# schematic.net
KiCad netlist of a schematic drawn in EasyEDA
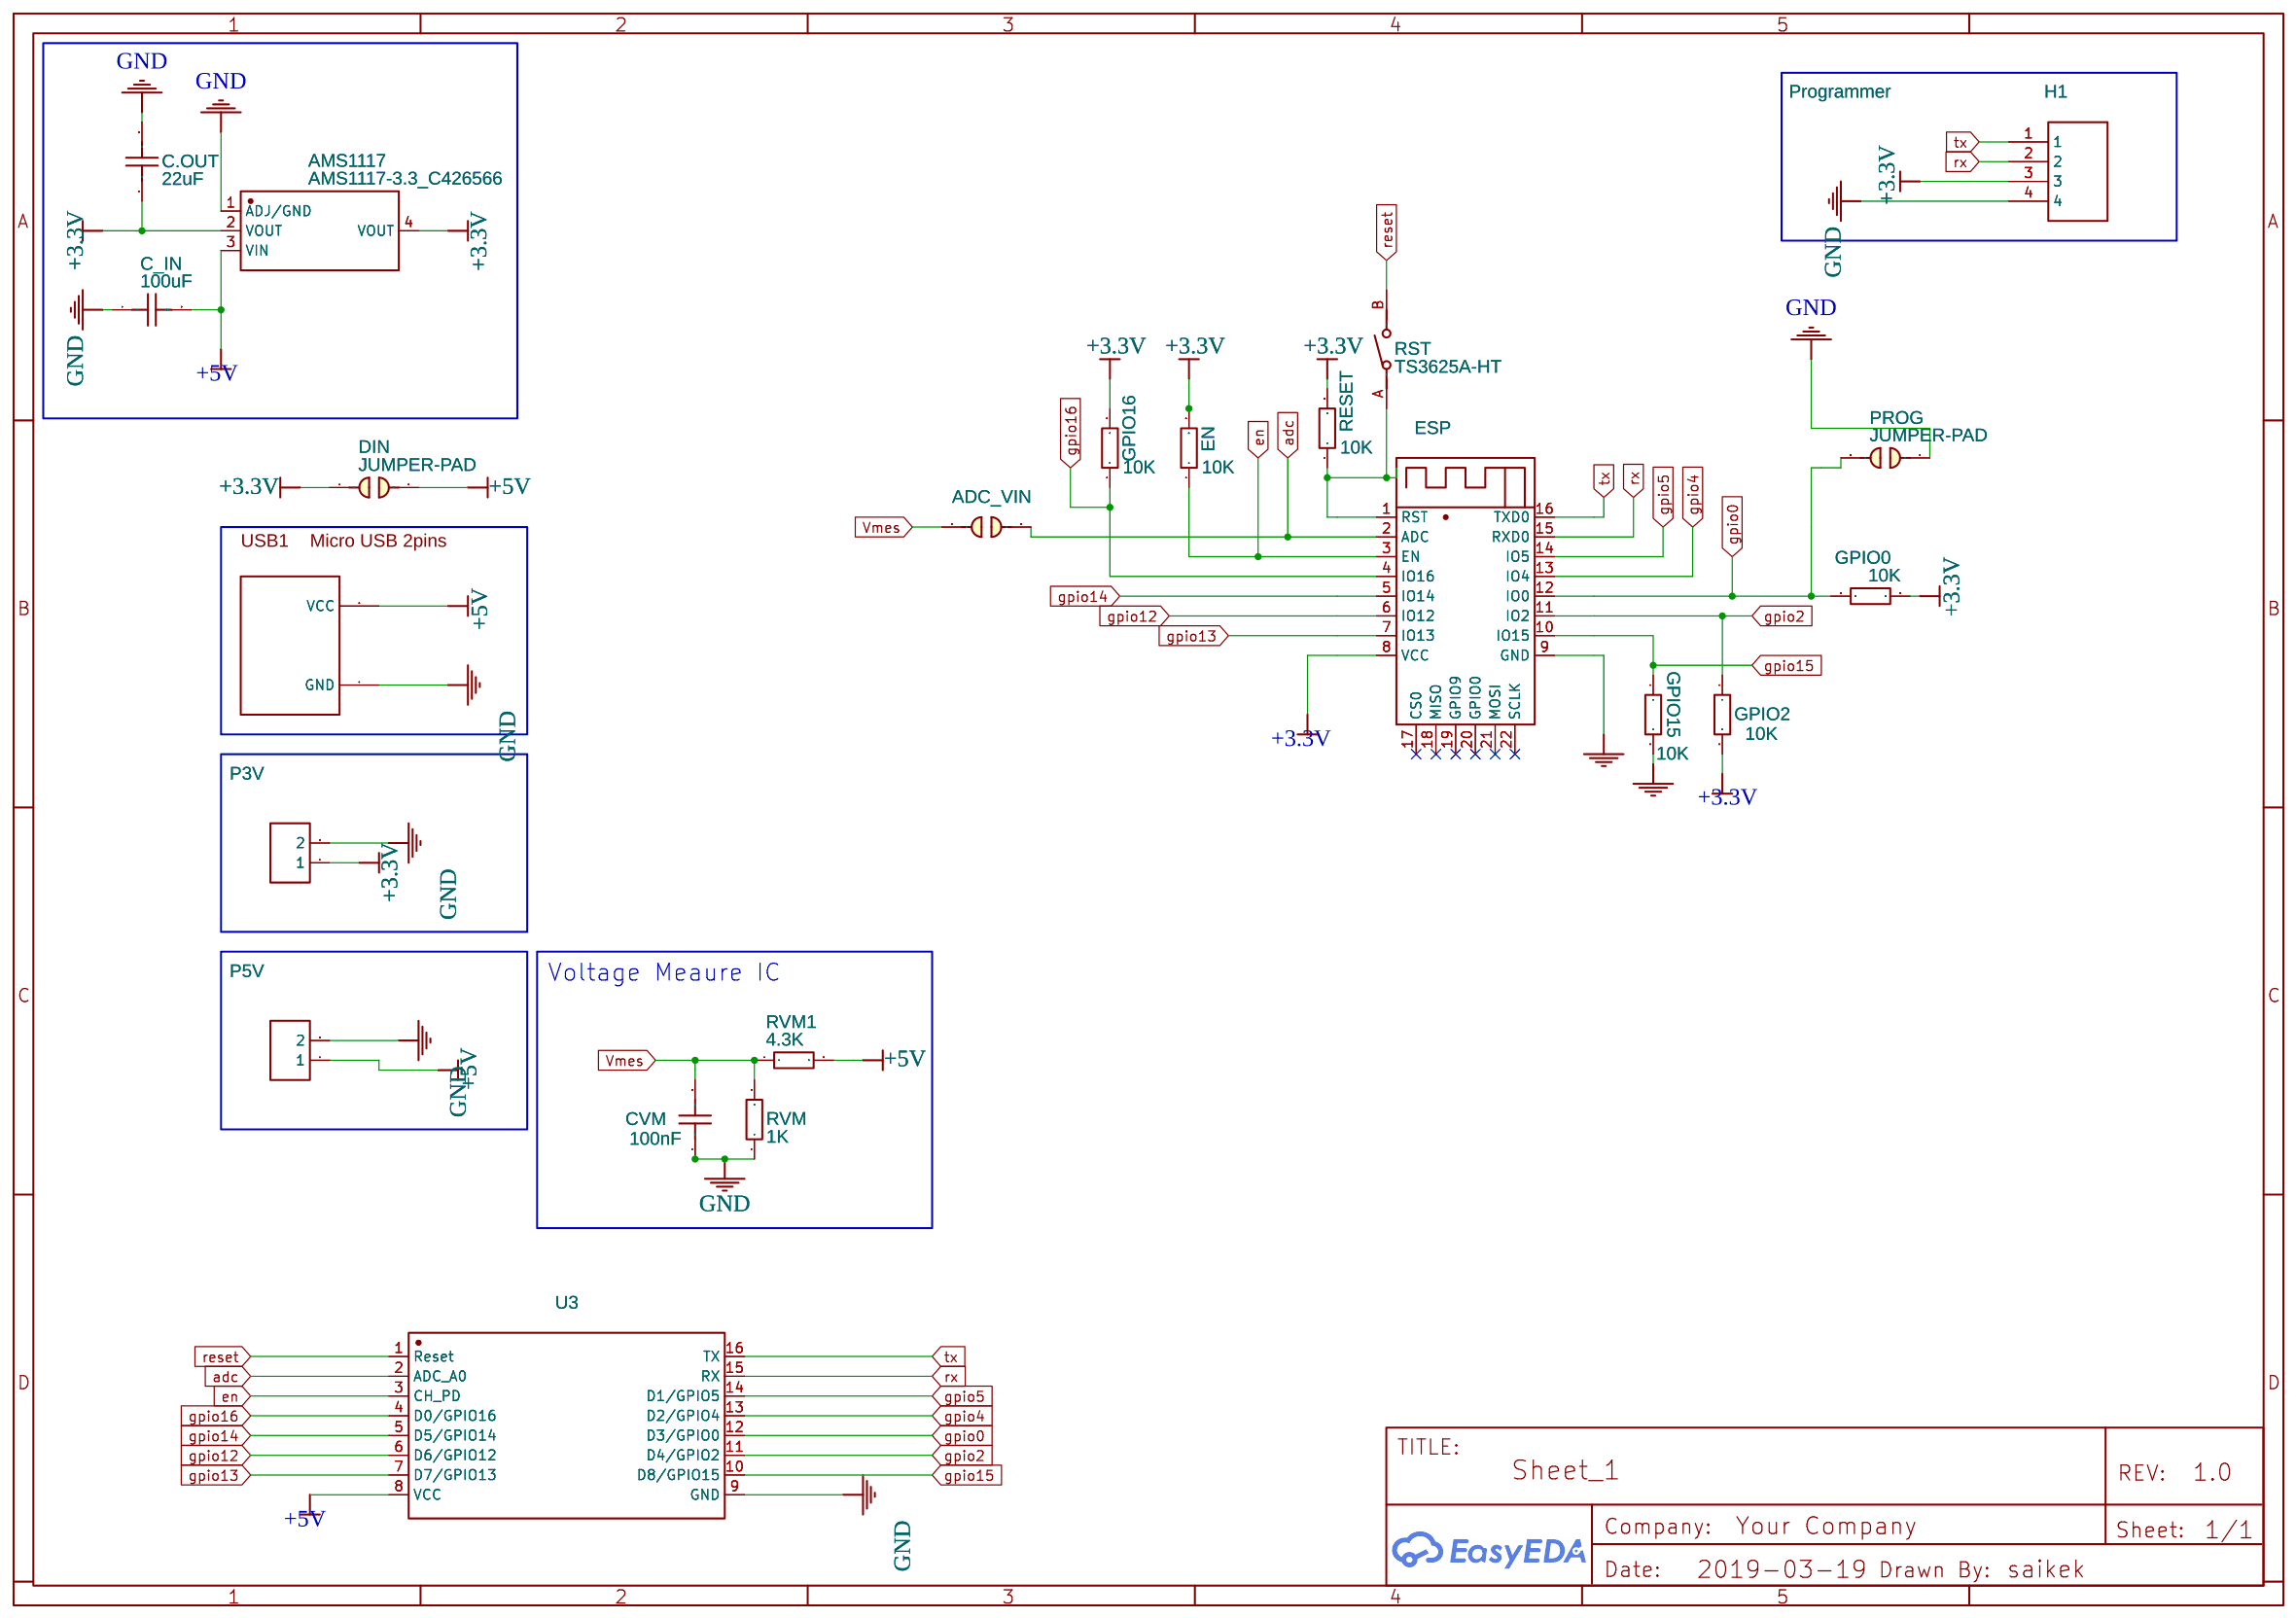
[diagram p0: schematic sheet]

(export (version "E")
  (design (tool "Eeschema 10.0.6"))
  (components
    (comp (ref "ADC_VIN") (value "JUMPER-PAD") (libsource (lib "") (part "JUMPER-PAD_1")))
    (comp (ref "AMS1117")
      (value "AMS1117-3.3_C426566")
      (fields
        (field (name "BOM_Manufacturer Part") "AMS1117-3.3")
        (field (name "BOM_Supplier Part") "C426566")
      )
      (libsource (lib "") (part "Unknown_155_110"))
    )
    (comp (ref "C.OUT")
      (value "22uF")
      (fields
        (field (name "BOM_Manufacturer Part") "LMK212BJ226MG-T")
        (field (name "BOM_Supplier Part") "C92814")
      )
      (libsource (lib "") (part "LMK212BJ226MG-T"))
    )
    (comp (ref "CVM")
      (value "100nF")
      (fields
        (field (name "BOM_Manufacturer Part") "FS31B107M6R3EPG")
        (field (name "BOM_Supplier Part") "C363564")
      )
      (libsource (lib "") (part "FS31B107M6R3EPG_1"))
    )
    (comp (ref "C_IN")
      (value "100uF")
      (fields
        (field (name "BOM_Manufacturer Part") "FS31B107M6R3EPG")
        (field (name "BOM_Supplier Part") "C363564")
      )
      (libsource (lib "") (part "FS31B107M6R3EPG"))
    )
    (comp (ref "DIN") (value "JUMPER-PAD") (libsource (lib "") (part "JUMPER-PAD_2")))
    (comp (ref "EN")
      (value "10K")
      (fields
        (field (name "BOM_Manufacturer Part") "QR1206J10KP05")
        (field (name "BOM_Supplier Part") "C176266")
      )
      (libsource (lib "") (part "QR1206J10KP05"))
    )
    (comp (ref "ESP")
      (value "WT8266-S5 ESP-12F")
      (fields (field (name "BOM_Supplier Part") "C477829"))
      (libsource (lib "") (part "WT8266-S5 ESP-12F"))
    )
    (comp (ref "GPIO0")
      (value "10K")
      (fields
        (field (name "BOM_Manufacturer Part") "QR1206J10KP05")
        (field (name "BOM_Supplier Part") "C176266")
      )
      (libsource (lib "") (part "QR1206J10KP05_6"))
    )
    (comp (ref "GPIO2")
      (value "10K")
      (fields
        (field (name "BOM_Manufacturer Part") "QR1206J10KP05")
        (field (name "BOM_Supplier Part") "C176266")
      )
      (libsource (lib "") (part "QR1206J10KP05_3"))
    )
    (comp (ref "GPIO15")
      (value "10K")
      (fields
        (field (name "BOM_Manufacturer Part") "QR1206J10KP05")
        (field (name "BOM_Supplier Part") "C176266")
      )
      (libsource (lib "") (part "QR1206J10KP05_3"))
    )
    (comp (ref "GPIO16")
      (value "10K")
      (fields
        (field (name "BOM_Manufacturer Part") "QR1206J10KP05")
        (field (name "BOM_Supplier Part") "C176266")
      )
      (libsource (lib "") (part "QR1206J10KP05_1"))
    )
    (comp (ref "H1")
      (value "Programmer")
      (fields
        (field (name "BOM_Manufacturer Part") "220S-1*4P H=8.5MM Ytype Gold-plated")
        (field (name "BOM_Supplier Part") "C124413")
      )
      (libsource (lib "") (part "Unknown_1035_80"))
    )
    (comp (ref "P3V")
      (value "Header-Female-2.54_1x2")
      (fields
        (field (name "BOM_Manufacturer Part") "2.54-1*2PFemale")
        (field (name "BOM_Supplier Part") "C49661")
      )
      (libsource (lib "") (part "Header-Female-2.54_1x2"))
    )
    (comp (ref "P5V")
      (value "Header-Female-2.54_1x2")
      (fields
        (field (name "BOM_Manufacturer Part") "2.54-1*2PFemale")
        (field (name "BOM_Supplier Part") "C49661")
      )
      (libsource (lib "") (part "Header-Female-2.54_1x2_1"))
    )
    (comp (ref "PROG") (value "JUMPER-PAD") (libsource (lib "") (part "JUMPER-PAD")))
    (comp (ref "RESET")
      (value "10K")
      (fields
        (field (name "BOM_Manufacturer Part") "QR1206J10KP05")
        (field (name "BOM_Supplier Part") "C176266")
      )
      (libsource (lib "") (part "QR1206J10KP05_5"))
    )
    (comp (ref "RST")
      (value "TS3625A-HT")
      (fields (field (name "BOM_Supplier Part") "C412368"))
      (libsource (lib "") (part "TS3625A-HT"))
    )
    (comp (ref "RVM")
      (value "1K")
      (fields
        (field (name "BOM_Manufacturer Part") "QR1206J10KP05")
        (field (name "BOM_Supplier Part") "C176266")
      )
      (libsource (lib "") (part "QR1206J10KP05_4"))
    )
    (comp (ref "RVM1")
      (value "4.3K")
      (fields
        (field (name "BOM_Manufacturer Part") "QR1206J10KP05")
        (field (name "BOM_Supplier Part") "C176266")
      )
      (libsource (lib "") (part "QR1206J10KP05_2"))
    )
    (comp (ref "U3") (value "Esp8266_witty") (libsource (lib "") (part "Unknown_280_670")))
    (comp (ref "U4") (value "MicroUSB 2 pins female") (libsource (lib "") (part "Unknown_145_320")))
  )
  (nets
    (net (code "1") (name "+3.3V") (class "Default")
      (node (ref "AMS1117") (pin "2") (pinfunction "VOUT_2") (pintype "unspecified"))
      (node (ref "AMS1117") (pin "4") (pinfunction "VOUT_4") (pintype "unspecified"))
      (node (ref "C.OUT") (pin "1") (pinfunction "1_1") (pintype "unspecified"))
      (node (ref "DIN") (pin "1") (pinfunction "1_1") (pintype "unspecified"))
      (node (ref "EN") (pin "2") (pinfunction "2_2") (pintype "unspecified"))
      (node (ref "ESP") (pin "8") (pinfunction "VCC_8") (pintype "unspecified"))
      (node (ref "GPIO0") (pin "2") (pinfunction "2_2") (pintype "unspecified"))
      (node (ref "GPIO16") (pin "2") (pinfunction "2_2") (pintype "unspecified"))
      (node (ref "GPIO2") (pin "2") (pinfunction "2_2") (pintype "unspecified"))
      (node (ref "H1") (pin "3") (pinfunction "3_3") (pintype "unspecified"))
      (node (ref "P3V") (pin "1") (pinfunction "1_1") (pintype "input"))
      (node (ref "RESET") (pin "2") (pinfunction "2_2") (pintype "unspecified"))
    )
    (net (code "2") (name "+5V") (class "Default")
      (node (ref "AMS1117") (pin "3") (pinfunction "VIN_3") (pintype "unspecified"))
      (node (ref "C_IN") (pin "2") (pinfunction "2_2") (pintype "unspecified"))
      (node (ref "DIN") (pin "2") (pinfunction "2_2") (pintype "unspecified"))
      (node (ref "P5V") (pin "1") (pinfunction "1_1") (pintype "input"))
      (node (ref "RVM1") (pin "2") (pinfunction "2_2") (pintype "unspecified"))
      (node (ref "U3") (pin "8") (pinfunction "VCC_8") (pintype "unspecified"))
      (node (ref "U4") (pin "2") (pinfunction "VCC_2") (pintype "unspecified"))
    )
    (net (code "3") (name "GND") (class "Default")
      (node (ref "AMS1117") (pin "1") (pinfunction "ADJ/GND_1") (pintype "unspecified"))
      (node (ref "C.OUT") (pin "2") (pinfunction "2_2") (pintype "unspecified"))
      (node (ref "CVM") (pin "1") (pinfunction "1_1") (pintype "unspecified"))
      (node (ref "C_IN") (pin "1") (pinfunction "1_1") (pintype "unspecified"))
      (node (ref "ESP") (pin "9") (pinfunction "GND_9") (pintype "unspecified"))
      (node (ref "GPIO15") (pin "2") (pinfunction "2_2") (pintype "unspecified"))
      (node (ref "H1") (pin "4") (pinfunction "4_4") (pintype "unspecified"))
      (node (ref "P3V") (pin "2") (pinfunction "2_2") (pintype "input"))
      (node (ref "P5V") (pin "2") (pinfunction "2_2") (pintype "input"))
      (node (ref "PROG") (pin "1") (pinfunction "1_1") (pintype "unspecified"))
      (node (ref "RVM") (pin "1") (pinfunction "1_1") (pintype "unspecified"))
      (node (ref "U3") (pin "9") (pinfunction "GND_9") (pintype "unspecified"))
      (node (ref "U4") (pin "1") (pinfunction "GND_1") (pintype "unspecified"))
    )
    (net (code "4") (name "Net-(ESP-RST)") (class "Default")
      (node (ref "ESP") (pin "1") (pinfunction "RST_1") (pintype "unspecified"))
      (node (ref "RESET") (pin "1") (pinfunction "1_1") (pintype "unspecified"))
      (node (ref "RST") (pin "A") (pinfunction "A_A") (pintype "unspecified"))
    )
    (net (code "5") (name "Vmes") (class "Default")
      (node (ref "ADC_VIN") (pin "1") (pinfunction "1_1") (pintype "unspecified"))
      (node (ref "CVM") (pin "2") (pinfunction "2_2") (pintype "unspecified"))
      (node (ref "RVM") (pin "2") (pinfunction "2_2") (pintype "unspecified"))
      (node (ref "RVM1") (pin "1") (pinfunction "1_1") (pintype "unspecified"))
    )
    (net (code "6") (name "adc") (class "Default")
      (node (ref "ADC_VIN") (pin "2") (pinfunction "2_2") (pintype "unspecified"))
      (node (ref "ESP") (pin "2") (pinfunction "ADC_2") (pintype "unspecified"))
      (node (ref "U3") (pin "2") (pinfunction "ADC_A0_2") (pintype "unspecified"))
    )
    (net (code "7") (name "en") (class "Default")
      (node (ref "EN") (pin "1") (pinfunction "1_1") (pintype "unspecified"))
      (node (ref "ESP") (pin "3") (pinfunction "EN_3") (pintype "unspecified"))
      (node (ref "U3") (pin "3") (pinfunction "CH_PD_3") (pintype "unspecified"))
    )
    (net (code "8") (name "gpio0") (class "Default")
      (node (ref "ESP") (pin "12") (pinfunction "IO0_12") (pintype "unspecified"))
      (node (ref "GPIO0") (pin "1") (pinfunction "1_1") (pintype "unspecified"))
      (node (ref "PROG") (pin "2") (pinfunction "2_2") (pintype "unspecified"))
      (node (ref "U3") (pin "12") (pinfunction "D3/GPIO0_12") (pintype "unspecified"))
    )
    (net (code "9") (name "gpio2") (class "Default")
      (node (ref "ESP") (pin "11") (pinfunction "IO2_11") (pintype "unspecified"))
      (node (ref "GPIO2") (pin "1") (pinfunction "1_1") (pintype "unspecified"))
      (node (ref "U3") (pin "11") (pinfunction "D4/GPIO2_11") (pintype "unspecified"))
    )
    (net (code "10") (name "gpio4") (class "Default")
      (node (ref "ESP") (pin "13") (pinfunction "IO4_13") (pintype "unspecified"))
      (node (ref "U3") (pin "13") (pinfunction "D2/GPIO4_13") (pintype "unspecified"))
    )
    (net (code "11") (name "gpio5") (class "Default")
      (node (ref "ESP") (pin "14") (pinfunction "IO5_14") (pintype "unspecified"))
      (node (ref "U3") (pin "14") (pinfunction "D1/GPIO5_14") (pintype "unspecified"))
    )
    (net (code "12") (name "gpio12") (class "Default")
      (node (ref "ESP") (pin "6") (pinfunction "IO12_6") (pintype "unspecified"))
      (node (ref "U3") (pin "6") (pinfunction "D6/GPIO12_6") (pintype "unspecified"))
    )
    (net (code "13") (name "gpio13") (class "Default")
      (node (ref "ESP") (pin "7") (pinfunction "IO13_7") (pintype "unspecified"))
      (node (ref "U3") (pin "7") (pinfunction "D7/GPIO13_7") (pintype "unspecified"))
    )
    (net (code "14") (name "gpio14") (class "Default")
      (node (ref "ESP") (pin "5") (pinfunction "IO14_5") (pintype "unspecified"))
      (node (ref "U3") (pin "5") (pinfunction "D5/GPIO14_5") (pintype "unspecified"))
    )
    (net (code "15") (name "gpio15") (class "Default")
      (node (ref "ESP") (pin "10") (pinfunction "IO15_10") (pintype "unspecified"))
      (node (ref "GPIO15") (pin "1") (pinfunction "1_1") (pintype "unspecified"))
      (node (ref "U3") (pin "10") (pinfunction "D8/GPIO15_10") (pintype "unspecified"))
    )
    (net (code "16") (name "gpio16") (class "Default")
      (node (ref "ESP") (pin "4") (pinfunction "IO16_4") (pintype "unspecified"))
      (node (ref "GPIO16") (pin "1") (pinfunction "1_1") (pintype "unspecified"))
      (node (ref "U3") (pin "4") (pinfunction "D0/GPIO16_4") (pintype "unspecified"))
    )
    (net (code "17") (name "reset") (class "Default")
      (node (ref "RST") (pin "B") (pinfunction "B_B") (pintype "unspecified"))
      (node (ref "U3") (pin "1") (pinfunction "Reset_1") (pintype "unspecified"))
    )
    (net (code "18") (name "rx") (class "Default")
      (node (ref "ESP") (pin "15") (pinfunction "RXD0_15") (pintype "unspecified"))
      (node (ref "H1") (pin "2") (pinfunction "2_2") (pintype "unspecified"))
      (node (ref "U3") (pin "15") (pinfunction "RX_15") (pintype "unspecified"))
    )
    (net (code "19") (name "tx") (class "Default")
      (node (ref "ESP") (pin "16") (pinfunction "TXD0_16") (pintype "unspecified"))
      (node (ref "H1") (pin "1") (pinfunction "1_1") (pintype "unspecified"))
      (node (ref "U3") (pin "16") (pinfunction "TX_16") (pintype "unspecified"))
    )
    (net (code "20") (name "unconnected-(ESP-CS0-Pad17)") (class "Default")
      (node (ref "ESP") (pin "17") (pinfunction "CS0_17") (pintype "unspecified+no_connect"))
    )
    (net (code "21") (name "unconnected-(ESP-GPIO0-Pad20)") (class "Default")
      (node (ref "ESP") (pin "20") (pinfunction "GPIO0_20") (pintype "unspecified+no_connect"))
    )
    (net (code "22") (name "unconnected-(ESP-GPIO9-Pad19)") (class "Default")
      (node (ref "ESP") (pin "19") (pinfunction "GPIO9_19") (pintype "unspecified+no_connect"))
    )
    (net (code "23") (name "unconnected-(ESP-MISO-Pad18)") (class "Default")
      (node (ref "ESP") (pin "18") (pinfunction "MISO_18") (pintype "unspecified+no_connect"))
    )
    (net (code "24") (name "unconnected-(ESP-MOSI-Pad21)") (class "Default")
      (node (ref "ESP") (pin "21") (pinfunction "MOSI_21") (pintype "unspecified+no_connect"))
    )
    (net (code "25") (name "unconnected-(ESP-SCLK-Pad22)") (class "Default")
      (node (ref "ESP") (pin "22") (pinfunction "SCLK_22") (pintype "unspecified+no_connect"))
    )
  )
)
